# 200W_4FET_Load_v11.net
KiCad netlist of a schematic drawn in EAGLE
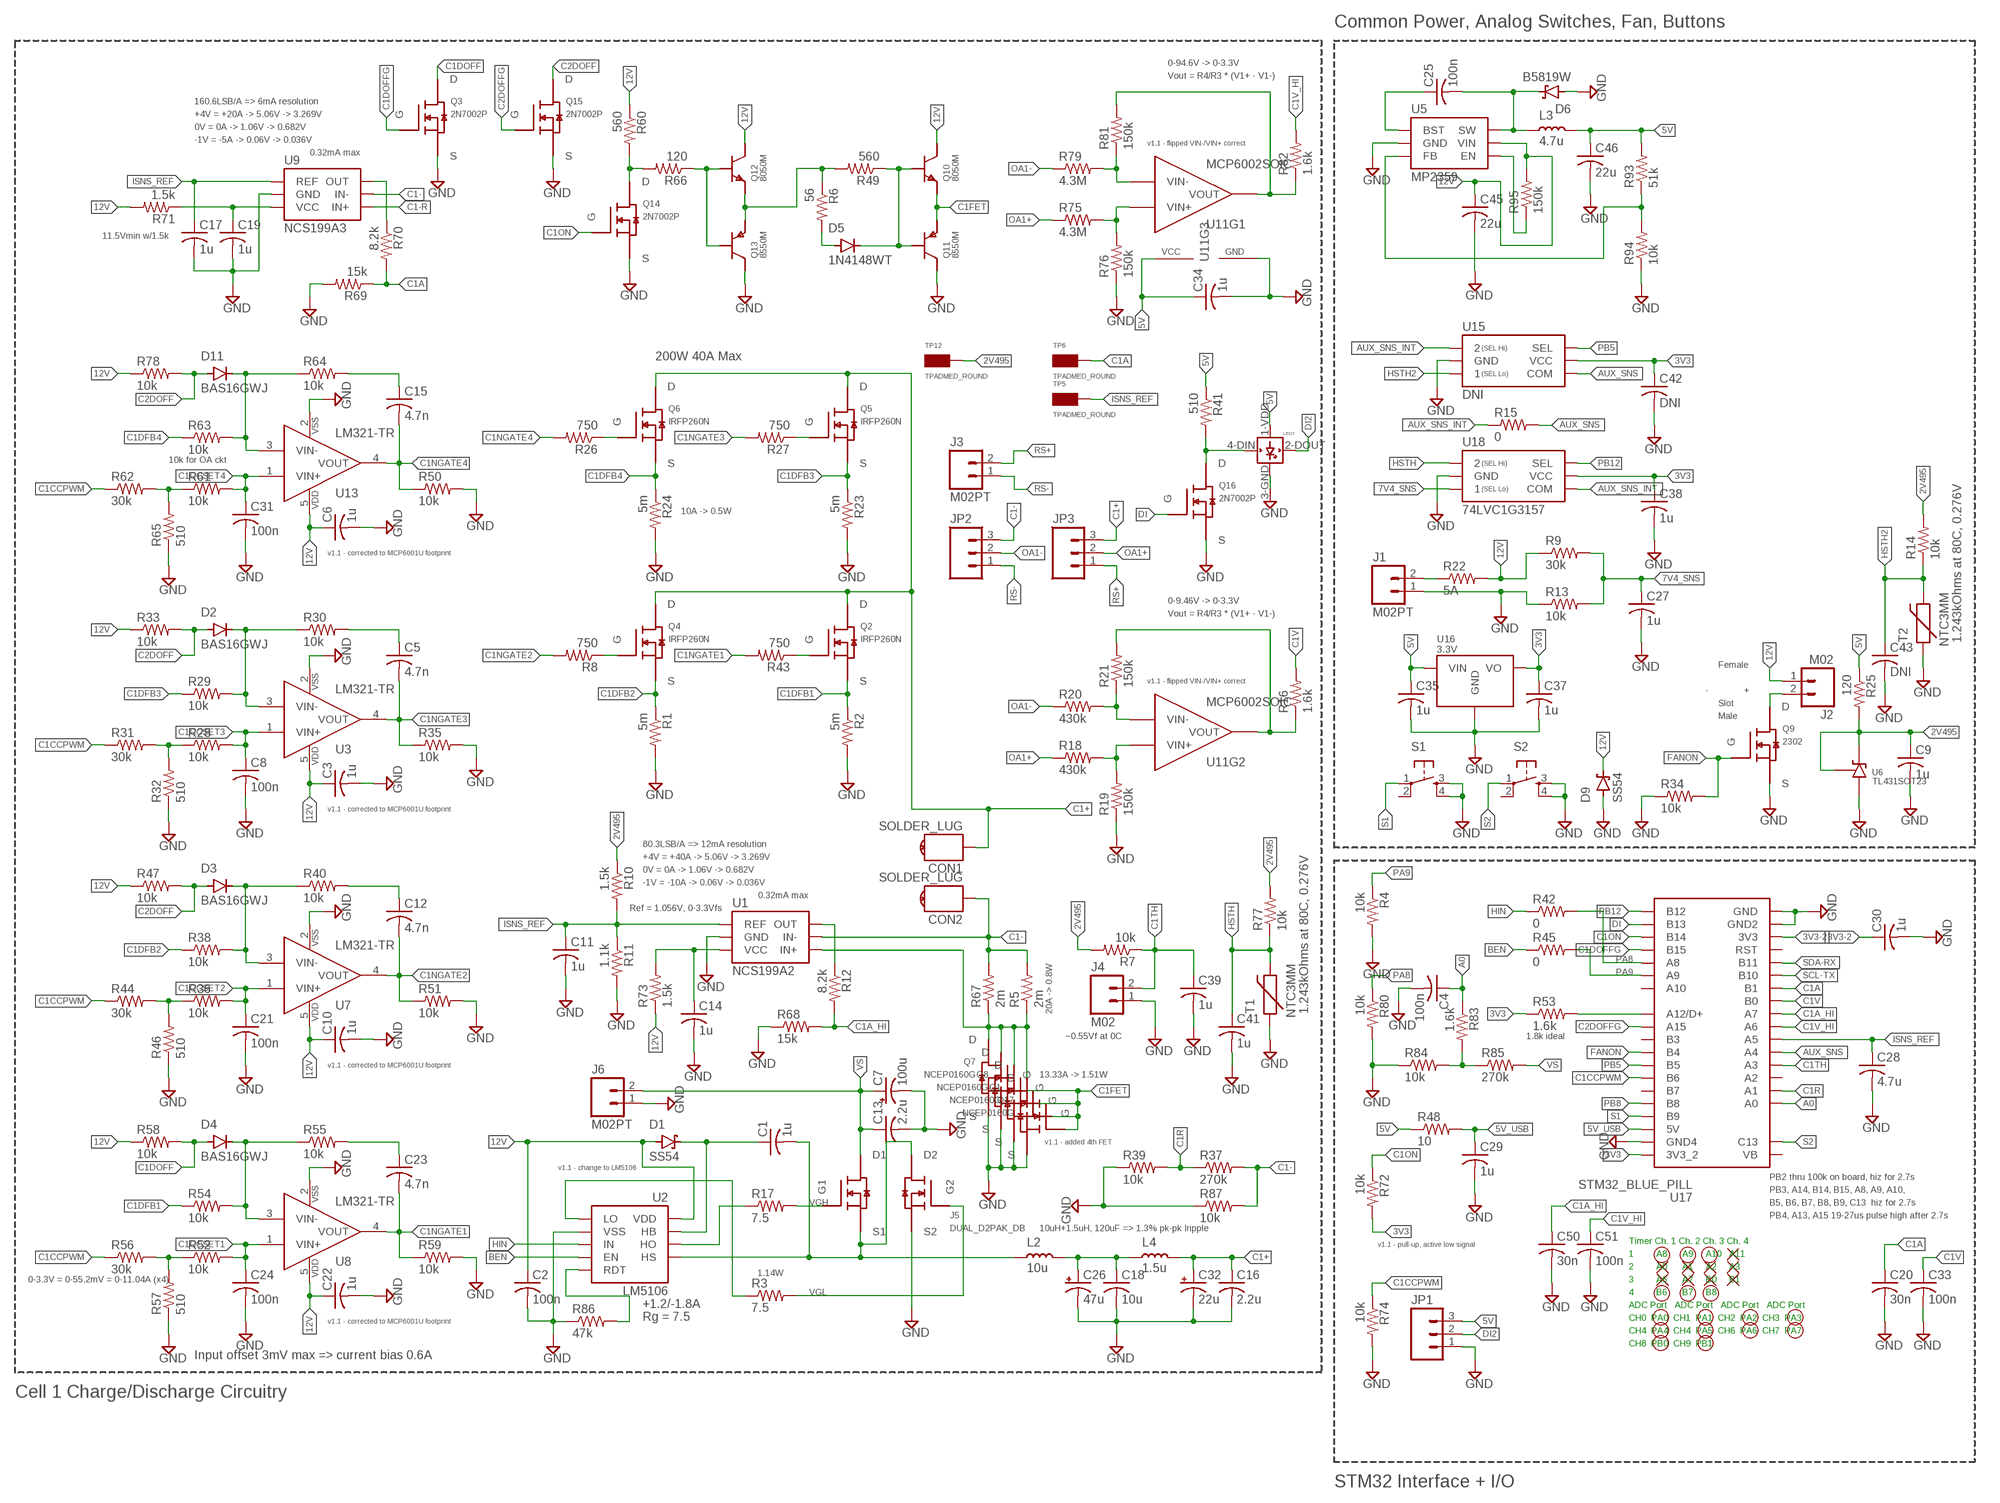
[diagram p0: schematic, sheet 1]

(export (version "E")
  (design (tool "Eeschema 10.0.6"))
  (components
    (comp (ref "C1")
      (value "1u")
      (footprint "eagle-import:C0603")
      (libsource (lib "eagle-import") (part "C-USC0603"))
    )
    (comp (ref "C2")
      (value "100n")
      (footprint "eagle-import:C0603")
      (libsource (lib "eagle-import") (part "C-USC0603"))
    )
    (comp (ref "C3")
      (value "1u")
      (footprint "eagle-import:C0402")
      (libsource (lib "eagle-import") (part "C-USC0402"))
    )
    (comp (ref "C4")
      (value "100n")
      (footprint "eagle-import:C0402")
      (libsource (lib "eagle-import") (part "C-USC0402"))
    )
    (comp (ref "C5")
      (value "4.7n")
      (footprint "eagle-import:C0402")
      (libsource (lib "eagle-import") (part "C-USC0402"))
    )
    (comp (ref "C6")
      (value "1u")
      (footprint "eagle-import:C0402")
      (libsource (lib "eagle-import") (part "C-USC0402"))
    )
    (comp (ref "C7")
      (value "100u")
      (footprint "eagle-import:E2,5-6E")
      (libsource (lib "eagle-import") (part "CPOL-USE2,5-6E"))
    )
    (comp (ref "C8")
      (value "100n")
      (footprint "eagle-import:C0402")
      (libsource (lib "eagle-import") (part "C-USC0402"))
    )
    (comp (ref "C9")
      (value "1u")
      (footprint "eagle-import:C0402")
      (libsource (lib "eagle-import") (part "C-USC0402"))
    )
    (comp (ref "C10")
      (value "1u")
      (footprint "eagle-import:C0402")
      (libsource (lib "eagle-import") (part "C-USC0402"))
    )
    (comp (ref "C11")
      (value "1u")
      (footprint "eagle-import:C0402")
      (libsource (lib "eagle-import") (part "C-USC0402"))
    )
    (comp (ref "C12")
      (value "4.7n")
      (footprint "eagle-import:C0402")
      (libsource (lib "eagle-import") (part "C-USC0402"))
    )
    (comp (ref "C13")
      (value "2.2u")
      (footprint "eagle-import:C1210")
      (libsource (lib "eagle-import") (part "C-USC1210"))
    )
    (comp (ref "C14")
      (value "1u")
      (footprint "eagle-import:C0402")
      (libsource (lib "eagle-import") (part "C-USC0402"))
    )
    (comp (ref "C15")
      (value "4.7n")
      (footprint "eagle-import:C0402")
      (libsource (lib "eagle-import") (part "C-USC0402"))
    )
    (comp (ref "C16")
      (value "2.2u")
      (footprint "eagle-import:C1210")
      (libsource (lib "eagle-import") (part "C-USC1210"))
    )
    (comp (ref "C17")
      (value "1u")
      (footprint "eagle-import:C0402")
      (libsource (lib "eagle-import") (part "C-USC0402"))
    )
    (comp (ref "C18")
      (value "10u")
      (footprint "eagle-import:C2220K")
      (libsource (lib "eagle-import") (part "C-USC2220K"))
    )
    (comp (ref "C19")
      (value "1u")
      (footprint "eagle-import:C0402")
      (libsource (lib "eagle-import") (part "C-USC0402"))
    )
    (comp (ref "C20")
      (value "30n")
      (footprint "eagle-import:C0402")
      (libsource (lib "eagle-import") (part "C-USC0402"))
    )
    (comp (ref "C21")
      (value "100n")
      (footprint "eagle-import:C0402")
      (libsource (lib "eagle-import") (part "C-USC0402"))
    )
    (comp (ref "C22")
      (value "1u")
      (footprint "eagle-import:C0402")
      (libsource (lib "eagle-import") (part "C-USC0402"))
    )
    (comp (ref "C23")
      (value "4.7n")
      (footprint "eagle-import:C0402")
      (libsource (lib "eagle-import") (part "C-USC0402"))
    )
    (comp (ref "C24")
      (value "100n")
      (footprint "eagle-import:C0402")
      (libsource (lib "eagle-import") (part "C-USC0402"))
    )
    (comp (ref "C25")
      (value "100n")
      (footprint "eagle-import:C0402")
      (libsource (lib "eagle-import") (part "C-USC0402"))
    )
    (comp (ref "C26")
      (value "47u")
      (footprint "eagle-import:E3,5-8")
      (libsource (lib "eagle-import") (part "CPOL-USE3.5-8"))
    )
    (comp (ref "C27")
      (value "1u")
      (footprint "eagle-import:C0402")
      (libsource (lib "eagle-import") (part "C-USC0402"))
    )
    (comp (ref "C28")
      (value "4.7u")
      (footprint "eagle-import:C0402")
      (libsource (lib "eagle-import") (part "C-USC0402"))
    )
    (comp (ref "C29")
      (value "1u")
      (footprint "eagle-import:C0402")
      (libsource (lib "eagle-import") (part "C-USC0402"))
    )
    (comp (ref "C30")
      (value "1u")
      (footprint "eagle-import:C0402")
      (libsource (lib "eagle-import") (part "C-USC0402"))
    )
    (comp (ref "C31")
      (value "100n")
      (footprint "eagle-import:C0402")
      (libsource (lib "eagle-import") (part "C-USC0402"))
    )
    (comp (ref "C32")
      (value "22u")
      (footprint "eagle-import:E2,5-6E")
      (libsource (lib "eagle-import") (part "CPOL-USE2,5-6E"))
    )
    (comp (ref "C33")
      (value "100n")
      (footprint "eagle-import:C0402")
      (libsource (lib "eagle-import") (part "C-USC0402"))
    )
    (comp (ref "C34")
      (value "1u")
      (footprint "eagle-import:C0402")
      (libsource (lib "eagle-import") (part "C-USC0402"))
    )
    (comp (ref "C35")
      (value "1u")
      (footprint "eagle-import:C0402")
      (libsource (lib "eagle-import") (part "C-USC0402"))
    )
    (comp (ref "C37")
      (value "1u")
      (footprint "eagle-import:C0402")
      (libsource (lib "eagle-import") (part "C-USC0402"))
    )
    (comp (ref "C38")
      (value "1u")
      (footprint "eagle-import:C0402")
      (libsource (lib "eagle-import") (part "C-USC0402"))
    )
    (comp (ref "C39")
      (value "1u")
      (footprint "eagle-import:C0402")
      (libsource (lib "eagle-import") (part "C-USC0402"))
    )
    (comp (ref "C41")
      (value "1u")
      (footprint "eagle-import:C0402")
      (libsource (lib "eagle-import") (part "C-USC0402"))
    )
    (comp (ref "C42")
      (value "DNI")
      (footprint "eagle-import:C0402")
      (libsource (lib "eagle-import") (part "C-USC0402"))
    )
    (comp (ref "C43")
      (value "DNI")
      (footprint "eagle-import:C0402")
      (libsource (lib "eagle-import") (part "C-USC0402"))
    )
    (comp (ref "C45")
      (value "22u")
      (footprint "eagle-import:C0805")
      (libsource (lib "eagle-import") (part "C-USC0805"))
    )
    (comp (ref "C46")
      (value "22u")
      (footprint "eagle-import:C0603")
      (libsource (lib "eagle-import") (part "C-USC0603"))
    )
    (comp (ref "C50")
      (value "30n")
      (footprint "eagle-import:C0402")
      (libsource (lib "eagle-import") (part "C-USC0402"))
    )
    (comp (ref "C51")
      (value "100n")
      (footprint "eagle-import:C0402")
      (libsource (lib "eagle-import") (part "C-USC0402"))
    )
    (comp (ref "CON1")
      (value "SOLDER_LUG")
      (footprint "eagle-import:M4_RA_SOLDTERM")
      (libsource (lib "eagle-import") (part "SOLDER_LUG"))
    )
    (comp (ref "CON2")
      (value "SOLDER_LUG")
      (footprint "eagle-import:M4_RA_SOLDTERM")
      (libsource (lib "eagle-import") (part "SOLDER_LUG"))
    )
    (comp (ref "D1")
      (value "SS54")
      (footprint "eagle-import:SMA")
      (libsource (lib "eagle-import") (part "SS54"))
    )
    (comp (ref "D2")
      (value "BAS16GWJ")
      (footprint "eagle-import:SOD323")
      (libsource (lib "eagle-import") (part "BAT60A"))
    )
    (comp (ref "D3")
      (value "BAS16GWJ")
      (footprint "eagle-import:SOD323")
      (libsource (lib "eagle-import") (part "BAT60A"))
    )
    (comp (ref "D4")
      (value "BAS16GWJ")
      (footprint "eagle-import:SOD323")
      (libsource (lib "eagle-import") (part "BAT60A"))
    )
    (comp (ref "D5")
      (value "1N4148WT")
      (footprint "eagle-import:SOD523")
      (libsource (lib "eagle-import") (part "1N4148WT"))
    )
    (comp (ref "D6")
      (value "B5819W")
      (footprint "eagle-import:SOD123W")
      (libsource (lib "eagle-import") (part "PMEG3020ER"))
    )
    (comp (ref "D9")
      (value "SS54")
      (footprint "eagle-import:SMA")
      (libsource (lib "eagle-import") (part "SS54"))
    )
    (comp (ref "D11")
      (value "BAS16GWJ")
      (footprint "eagle-import:SOD323")
      (libsource (lib "eagle-import") (part "BAT60A"))
    )
    (comp (ref "J1")
      (value "M02PT")
      (footprint "eagle-import:PHOENIXCONTACT1935161")
      (libsource (lib "eagle-import") (part "M02PT"))
    )
    (comp (ref "J2")
      (value "M02")
      (footprint "eagle-import:B2B-XH-A")
      (libsource (lib "eagle-import") (part "M02"))
    )
    (comp (ref "J3")
      (value "M02PT")
      (footprint "eagle-import:PHOENIXCONTACT1935161")
      (libsource (lib "eagle-import") (part "M02PT"))
    )
    (comp (ref "J4")
      (value "M02")
      (footprint "eagle-import:B2B-XH-A")
      (libsource (lib "eagle-import") (part "M02"))
    )
    (comp (ref "J5")
      (value "DUAL_D2PAK_DB")
      (footprint "eagle-import:DUAL_D2PAK_DB")
      (libsource (lib "eagle-import") (part "DUAL_D2PAK_DB"))
    )
    (comp (ref "J6")
      (value "M02PT")
      (footprint "eagle-import:PHOENIXCONTACT1935161")
      (libsource (lib "eagle-import") (part "M02PT"))
    )
    (comp (ref "JP1")
      (value "M03PTH")
      (footprint "eagle-import:1X03")
      (libsource (lib "eagle-import") (part "M03PTH"))
    )
    (comp (ref "JP2")
      (value "M03PTH")
      (footprint "eagle-import:1X03")
      (libsource (lib "eagle-import") (part "M03PTH"))
    )
    (comp (ref "JP3")
      (value "M03PTH")
      (footprint "eagle-import:1X03")
      (libsource (lib "eagle-import") (part "M03PTH"))
    )
    (comp (ref "L2")
      (value "10u")
      (footprint "eagle-import:INDUCTOR_13.8X12.7")
      (libsource (lib "eagle-import") (part "INDUCTOR13P8"))
    )
    (comp (ref "L3")
      (value "4.7u")
      (footprint "eagle-import:0805")
      (libsource (lib "eagle-import") (part "INDUCTOR0805"))
    )
    (comp (ref "L4")
      (value "1.5u")
      (footprint "eagle-import:INDUCTOR_7.4X6.6MM")
      (libsource (lib "eagle-import") (part "INDUCTOR"))
    )
    (comp (ref "LED7")
      (value "WS2812B")
      (footprint "eagle-import:WS2812B")
      (libsource (lib "eagle-import") (part "WS2812B"))
    )
    (comp (ref "Q1")
      (value "NCEP0160G")
      (footprint "eagle-import:DFN5X6-8L")
      (libsource (lib "eagle-import") (part "NCEP0160G"))
    )
    (comp (ref "Q2")
      (value "IRFP260N")
      (footprint "eagle-import:TO-247")
      (libsource (lib "eagle-import") (part "IRFP260N"))
    )
    (comp (ref "Q3")
      (value "2N7002P")
      (footprint "eagle-import:SOT23")
      (libsource (lib "eagle-import") (part "2N7002P"))
    )
    (comp (ref "Q4")
      (value "IRFP260N")
      (footprint "eagle-import:TO-247")
      (libsource (lib "eagle-import") (part "IRFP260N"))
    )
    (comp (ref "Q5")
      (value "IRFP260N")
      (footprint "eagle-import:TO-247")
      (libsource (lib "eagle-import") (part "IRFP260N"))
    )
    (comp (ref "Q6")
      (value "IRFP260N")
      (footprint "eagle-import:TO-247")
      (libsource (lib "eagle-import") (part "IRFP260N"))
    )
    (comp (ref "Q7")
      (value "NCEP0160G")
      (footprint "eagle-import:DFN5X6-8L")
      (libsource (lib "eagle-import") (part "NCEP0160G"))
    )
    (comp (ref "Q8")
      (value "NCEP0160G")
      (footprint "eagle-import:DFN5X6-8L")
      (libsource (lib "eagle-import") (part "NCEP0160G"))
    )
    (comp (ref "Q9")
      (value "2302")
      (footprint "eagle-import:SOT23")
      (libsource (lib "eagle-import") (part "2N7002P"))
    )
    (comp (ref "Q10")
      (value "8050M")
      (footprint "eagle-import:SOT23")
      (libsource (lib "eagle-import") (part "8050M"))
    )
    (comp (ref "Q11")
      (value "8550M")
      (footprint "eagle-import:SOT23")
      (libsource (lib "eagle-import") (part "8550M"))
    )
    (comp (ref "Q12")
      (value "8050M")
      (footprint "eagle-import:SOT23")
      (libsource (lib "eagle-import") (part "8050M"))
    )
    (comp (ref "Q13")
      (value "8550M")
      (footprint "eagle-import:SOT23")
      (libsource (lib "eagle-import") (part "8550M"))
    )
    (comp (ref "Q14")
      (value "2N7002P")
      (footprint "eagle-import:SOT23")
      (libsource (lib "eagle-import") (part "2N7002P"))
    )
    (comp (ref "Q15")
      (value "2N7002P")
      (footprint "eagle-import:SOT23")
      (libsource (lib "eagle-import") (part "2N7002P"))
    )
    (comp (ref "Q16")
      (value "2N7002P")
      (footprint "eagle-import:SOT23")
      (libsource (lib "eagle-import") (part "2N7002P"))
    )
    (comp (ref "Q17")
      (value "NCEP0160G")
      (footprint "eagle-import:DFN5X6-8L")
      (libsource (lib "eagle-import") (part "NCEP0160G"))
    )
    (comp (ref "R1")
      (value "5m")
      (footprint "eagle-import:R1206")
      (libsource (lib "eagle-import") (part "R-US_R1206"))
    )
    (comp (ref "R2")
      (value "5m")
      (footprint "eagle-import:R1206")
      (libsource (lib "eagle-import") (part "R-US_R1206"))
    )
    (comp (ref "R3")
      (value "7.5")
      (footprint "eagle-import:R2512")
      (libsource (lib "eagle-import") (part "R-US_R2512"))
    )
    (comp (ref "R4")
      (value "10k")
      (footprint "eagle-import:R0402")
      (libsource (lib "eagle-import") (part "R-US_R0402"))
    )
    (comp (ref "R5")
      (value "2m")
      (footprint "eagle-import:R2512")
      (libsource (lib "eagle-import") (part "R-US_R2512"))
    )
    (comp (ref "R6")
      (value "56")
      (footprint "eagle-import:R0402")
      (libsource (lib "eagle-import") (part "R-US_R0402"))
    )
    (comp (ref "R7")
      (value "10k")
      (footprint "eagle-import:R0402")
      (libsource (lib "eagle-import") (part "R-US_R0402"))
    )
    (comp (ref "R8")
      (value "750")
      (footprint "eagle-import:R0402")
      (libsource (lib "eagle-import") (part "R-US_R0402"))
    )
    (comp (ref "R9")
      (value "30k")
      (footprint "eagle-import:R0402")
      (libsource (lib "eagle-import") (part "R-US_R0402"))
    )
    (comp (ref "R10")
      (value "1.5k")
      (footprint "eagle-import:R0402")
      (libsource (lib "eagle-import") (part "R-US_R0402"))
    )
    (comp (ref "R11")
      (value "1.1k")
      (footprint "eagle-import:R0402")
      (libsource (lib "eagle-import") (part "R-US_R0402"))
    )
    (comp (ref "R12")
      (value "8.2k")
      (footprint "eagle-import:R0402")
      (libsource (lib "eagle-import") (part "R-US_R0402"))
    )
    (comp (ref "R13")
      (value "10k")
      (footprint "eagle-import:R0402")
      (libsource (lib "eagle-import") (part "R-US_R0402"))
    )
    (comp (ref "R14")
      (value "10k")
      (footprint "eagle-import:R0402")
      (libsource (lib "eagle-import") (part "R-US_R0402"))
    )
    (comp (ref "R15")
      (value "0")
      (footprint "eagle-import:R0402")
      (libsource (lib "eagle-import") (part "R-US_R0402"))
    )
    (comp (ref "R16")
      (value "1.6k")
      (footprint "eagle-import:R0402")
      (libsource (lib "eagle-import") (part "R-US_R0402"))
    )
    (comp (ref "R17")
      (value "7.5")
      (footprint "eagle-import:R2512")
      (libsource (lib "eagle-import") (part "R-US_R2512"))
    )
    (comp (ref "R18")
      (value "430k")
      (footprint "eagle-import:R0402")
      (libsource (lib "eagle-import") (part "R-US_R0402"))
    )
    (comp (ref "R19")
      (value "150k")
      (footprint "eagle-import:R0402")
      (libsource (lib "eagle-import") (part "R-US_R0402"))
    )
    (comp (ref "R20")
      (value "430k")
      (footprint "eagle-import:R0402")
      (libsource (lib "eagle-import") (part "R-US_R0402"))
    )
    (comp (ref "R21")
      (value "150k")
      (footprint "eagle-import:R0402")
      (libsource (lib "eagle-import") (part "R-US_R0402"))
    )
    (comp (ref "R22")
      (value "5A")
      (footprint "eagle-import:R1206")
      (libsource (lib "eagle-import") (part "R-US_R1206"))
    )
    (comp (ref "R23")
      (value "5m")
      (footprint "eagle-import:R1206")
      (libsource (lib "eagle-import") (part "R-US_R1206"))
    )
    (comp (ref "R24")
      (value "5m")
      (footprint "eagle-import:R1206")
      (libsource (lib "eagle-import") (part "R-US_R1206"))
    )
    (comp (ref "R25")
      (value "120")
      (footprint "eagle-import:R0402")
      (libsource (lib "eagle-import") (part "R-US_R0402"))
    )
    (comp (ref "R26")
      (value "750")
      (footprint "eagle-import:R0402")
      (libsource (lib "eagle-import") (part "R-US_R0402"))
    )
    (comp (ref "R27")
      (value "750")
      (footprint "eagle-import:R0402")
      (libsource (lib "eagle-import") (part "R-US_R0402"))
    )
    (comp (ref "R28")
      (value "10k")
      (footprint "eagle-import:R0402")
      (libsource (lib "eagle-import") (part "R-US_R0402"))
    )
    (comp (ref "R29")
      (value "10k")
      (footprint "eagle-import:R0402")
      (libsource (lib "eagle-import") (part "R-US_R0402"))
    )
    (comp (ref "R30")
      (value "10k")
      (footprint "eagle-import:R0402")
      (libsource (lib "eagle-import") (part "R-US_R0402"))
    )
    (comp (ref "R31")
      (value "30k")
      (footprint "eagle-import:R0402")
      (libsource (lib "eagle-import") (part "R-US_R0402"))
    )
    (comp (ref "R32")
      (value "510")
      (footprint "eagle-import:R0402")
      (libsource (lib "eagle-import") (part "R-US_R0402"))
    )
    (comp (ref "R33")
      (value "10k")
      (footprint "eagle-import:R0402")
      (libsource (lib "eagle-import") (part "R-US_R0402"))
    )
    (comp (ref "R34")
      (value "10k")
      (footprint "eagle-import:R0402")
      (libsource (lib "eagle-import") (part "R-US_R0402"))
    )
    (comp (ref "R35")
      (value "10k")
      (footprint "eagle-import:R0402")
      (libsource (lib "eagle-import") (part "R-US_R0402"))
    )
    (comp (ref "R36")
      (value "10k")
      (footprint "eagle-import:R0402")
      (libsource (lib "eagle-import") (part "R-US_R0402"))
    )
    (comp (ref "R37")
      (value "270k")
      (footprint "eagle-import:R0402")
      (libsource (lib "eagle-import") (part "R-US_R0402"))
    )
    (comp (ref "R38")
      (value "10k")
      (footprint "eagle-import:R0402")
      (libsource (lib "eagle-import") (part "R-US_R0402"))
    )
    (comp (ref "R39")
      (value "10k")
      (footprint "eagle-import:R0402")
      (libsource (lib "eagle-import") (part "R-US_R0402"))
    )
    (comp (ref "R40")
      (value "10k")
      (footprint "eagle-import:R0402")
      (libsource (lib "eagle-import") (part "R-US_R0402"))
    )
    (comp (ref "R41")
      (value "510")
      (footprint "eagle-import:R0402")
      (libsource (lib "eagle-import") (part "R-US_R0402"))
    )
    (comp (ref "R42")
      (value "0")
      (footprint "eagle-import:R0402")
      (libsource (lib "eagle-import") (part "R-US_R0402"))
    )
    (comp (ref "R43")
      (value "750")
      (footprint "eagle-import:R0402")
      (libsource (lib "eagle-import") (part "R-US_R0402"))
    )
    (comp (ref "R44")
      (value "30k")
      (footprint "eagle-import:R0402")
      (libsource (lib "eagle-import") (part "R-US_R0402"))
    )
    (comp (ref "R45")
      (value "0")
      (footprint "eagle-import:R0402")
      (libsource (lib "eagle-import") (part "R-US_R0402"))
    )
    (comp (ref "R46")
      (value "510")
      (footprint "eagle-import:R0402")
      (libsource (lib "eagle-import") (part "R-US_R0402"))
    )
    (comp (ref "R47")
      (value "10k")
      (footprint "eagle-import:R0402")
      (libsource (lib "eagle-import") (part "R-US_R0402"))
    )
    (comp (ref "R48")
      (value "10")
      (footprint "eagle-import:R0402")
      (libsource (lib "eagle-import") (part "R-US_R0402"))
    )
    (comp (ref "R49")
      (value "560")
      (footprint "eagle-import:R0402")
      (libsource (lib "eagle-import") (part "R-US_R0402"))
    )
    (comp (ref "R50")
      (value "10k")
      (footprint "eagle-import:R0402")
      (libsource (lib "eagle-import") (part "R-US_R0402"))
    )
    (comp (ref "R51")
      (value "10k")
      (footprint "eagle-import:R0402")
      (libsource (lib "eagle-import") (part "R-US_R0402"))
    )
    (comp (ref "R52")
      (value "10k")
      (footprint "eagle-import:R0402")
      (libsource (lib "eagle-import") (part "R-US_R0402"))
    )
    (comp (ref "R53")
      (value "1.6k")
      (footprint "eagle-import:R0402")
      (libsource (lib "eagle-import") (part "R-US_R0402"))
    )
    (comp (ref "R54")
      (value "10k")
      (footprint "eagle-import:R0402")
      (libsource (lib "eagle-import") (part "R-US_R0402"))
    )
    (comp (ref "R55")
      (value "10k")
      (footprint "eagle-import:R0402")
      (libsource (lib "eagle-import") (part "R-US_R0402"))
    )
    (comp (ref "R56")
      (value "30k")
      (footprint "eagle-import:R0402")
      (libsource (lib "eagle-import") (part "R-US_R0402"))
    )
    (comp (ref "R57")
      (value "510")
      (footprint "eagle-import:R0402")
      (libsource (lib "eagle-import") (part "R-US_R0402"))
    )
    (comp (ref "R58")
      (value "10k")
      (footprint "eagle-import:R0402")
      (libsource (lib "eagle-import") (part "R-US_R0402"))
    )
    (comp (ref "R59")
      (value "10k")
      (footprint "eagle-import:R0402")
      (libsource (lib "eagle-import") (part "R-US_R0402"))
    )
    (comp (ref "R60")
      (value "560")
      (footprint "eagle-import:R0402")
      (libsource (lib "eagle-import") (part "R-US_R0402"))
    )
    (comp (ref "R61")
      (value "10k")
      (footprint "eagle-import:R0402")
      (libsource (lib "eagle-import") (part "R-US_R0402"))
    )
    (comp (ref "R62")
      (value "30k")
      (footprint "eagle-import:R0402")
      (libsource (lib "eagle-import") (part "R-US_R0402"))
    )
    (comp (ref "R63")
      (value "10k")
      (footprint "eagle-import:R0402")
      (libsource (lib "eagle-import") (part "R-US_R0402"))
    )
    (comp (ref "R64")
      (value "10k")
      (footprint "eagle-import:R0402")
      (libsource (lib "eagle-import") (part "R-US_R0402"))
    )
    (comp (ref "R65")
      (value "510")
      (footprint "eagle-import:R0402")
      (libsource (lib "eagle-import") (part "R-US_R0402"))
    )
    (comp (ref "R66")
      (value "120")
      (footprint "eagle-import:R0402")
      (libsource (lib "eagle-import") (part "R-US_R0402"))
    )
    (comp (ref "R67")
      (value "2m")
      (footprint "eagle-import:R2512")
      (libsource (lib "eagle-import") (part "R-US_R2512"))
    )
    (comp (ref "R68")
      (value "15k")
      (footprint "eagle-import:R0402")
      (libsource (lib "eagle-import") (part "R-US_R0402"))
    )
    (comp (ref "R69")
      (value "15k")
      (footprint "eagle-import:R0402")
      (libsource (lib "eagle-import") (part "R-US_R0402"))
    )
    (comp (ref "R70")
      (value "8.2k")
      (footprint "eagle-import:R0402")
      (libsource (lib "eagle-import") (part "R-US_R0402"))
    )
    (comp (ref "R71")
      (value "1.5k")
      (footprint "eagle-import:R0402")
      (libsource (lib "eagle-import") (part "R-US_R0402"))
    )
    (comp (ref "R72")
      (value "10k")
      (footprint "eagle-import:R0402")
      (libsource (lib "eagle-import") (part "R-US_R0402"))
    )
    (comp (ref "R73")
      (value "1.5k")
      (footprint "eagle-import:R0402")
      (libsource (lib "eagle-import") (part "R-US_R0402"))
    )
    (comp (ref "R74")
      (value "10k")
      (footprint "eagle-import:R0402")
      (libsource (lib "eagle-import") (part "R-US_R0402"))
    )
    (comp (ref "R75")
      (value "4.3M")
      (footprint "eagle-import:R0402")
      (libsource (lib "eagle-import") (part "R-US_R0402"))
    )
    (comp (ref "R76")
      (value "150k")
      (footprint "eagle-import:R0402")
      (libsource (lib "eagle-import") (part "R-US_R0402"))
    )
    (comp (ref "R77")
      (value "10k")
      (footprint "eagle-import:R0402")
      (libsource (lib "eagle-import") (part "R-US_R0402"))
    )
    (comp (ref "R78")
      (value "10k")
      (footprint "eagle-import:R0402")
      (libsource (lib "eagle-import") (part "R-US_R0402"))
    )
    (comp (ref "R79")
      (value "4.3M")
      (footprint "eagle-import:R0402")
      (libsource (lib "eagle-import") (part "R-US_R0402"))
    )
    (comp (ref "R80")
      (value "10k")
      (footprint "eagle-import:R0402")
      (libsource (lib "eagle-import") (part "R-US_R0402"))
    )
    (comp (ref "R81")
      (value "150k")
      (footprint "eagle-import:R0402")
      (libsource (lib "eagle-import") (part "R-US_R0402"))
    )
    (comp (ref "R82")
      (value "1.6k")
      (footprint "eagle-import:R0402")
      (libsource (lib "eagle-import") (part "R-US_R0402"))
    )
    (comp (ref "R83")
      (value "1.6k")
      (footprint "eagle-import:R0402")
      (libsource (lib "eagle-import") (part "R-US_R0402"))
    )
    (comp (ref "R84")
      (value "10k")
      (footprint "eagle-import:R0402")
      (libsource (lib "eagle-import") (part "R-US_R0402"))
    )
    (comp (ref "R85")
      (value "270k")
      (footprint "eagle-import:R0402")
      (libsource (lib "eagle-import") (part "R-US_R0402"))
    )
    (comp (ref "R86")
      (value "47k")
      (footprint "eagle-import:R0402")
      (libsource (lib "eagle-import") (part "R-US_R0402"))
    )
    (comp (ref "R87")
      (value "10k")
      (footprint "eagle-import:R1206")
      (libsource (lib "eagle-import") (part "R-US_R1206"))
    )
    (comp (ref "R93")
      (value "51k")
      (footprint "eagle-import:R0402")
      (libsource (lib "eagle-import") (part "R-US_R0402"))
    )
    (comp (ref "R94")
      (value "10k")
      (footprint "eagle-import:R0402")
      (libsource (lib "eagle-import") (part "R-US_R0402"))
    )
    (comp (ref "R95")
      (value "150k")
      (footprint "eagle-import:R0402")
      (libsource (lib "eagle-import") (part "R-US_R0402"))
    )
    (comp (ref "S1")
      (value "TAC_SWITCHSMD")
      (footprint "eagle-import:TACTILE_SWITCH_SMD")
      (libsource (lib "eagle-import") (part "TAC_SWITCHSMD"))
    )
    (comp (ref "S2")
      (value "TAC_SWITCHSMD")
      (footprint "eagle-import:TACTILE_SWITCH_SMD")
      (libsource (lib "eagle-import") (part "TAC_SWITCHSMD"))
    )
    (comp (ref "T1")
      (value "NTC3MM")
      (footprint "eagle-import:THERMISTOR_3MMX3MM")
      (libsource (lib "eagle-import") (part "PTCNTC3MM"))
    )
    (comp (ref "T2")
      (value "NTC3MM")
      (footprint "eagle-import:THERMISTOR_3MMX3MM")
      (libsource (lib "eagle-import") (part "PTCNTC3MM"))
    )
    (comp (ref "TP5")
      (value "TPADMED_ROUND")
      (footprint "eagle-import:TPAD_MED_ROUND")
      (libsource (lib "eagle-import") (part "TPADMED_ROUND"))
    )
    (comp (ref "TP6")
      (value "TPADMED_ROUND")
      (footprint "eagle-import:TPAD_MED_ROUND")
      (libsource (lib "eagle-import") (part "TPADMED_ROUND"))
    )
    (comp (ref "TP12")
      (value "TPADMED_ROUND")
      (footprint "eagle-import:TPAD_MED_ROUND")
      (libsource (lib "eagle-import") (part "TPADMED_ROUND"))
    )
    (comp (ref "U1")
      (value "NCS199A2")
      (footprint "eagle-import:SOT-363")
      (libsource (lib "eagle-import") (part "INA214"))
    )
    (comp (ref "U2")
      (value "LM5106")
      (footprint "eagle-import:10-TSSOP")
      (libsource (lib "eagle-import") (part "LM5106"))
    )
    (comp (ref "U3")
      (value "LM321-TR")
      (footprint "eagle-import:SOT23-5")
      (libsource (lib "eagle-import") (part "MCP6001U"))
    )
    (comp (ref "U5")
      (value "MP2359")
      (footprint "eagle-import:SOT23-6")
      (libsource (lib "eagle-import") (part "JW5052C"))
    )
    (comp (ref "U6")
      (value "TL431SOT23")
      (footprint "eagle-import:SOT23")
      (libsource (lib "eagle-import") (part "TL431SOT23"))
    )
    (comp (ref "U7")
      (value "LM321-TR")
      (footprint "eagle-import:SOT23-5")
      (libsource (lib "eagle-import") (part "MCP6001U"))
    )
    (comp (ref "U8")
      (value "LM321-TR")
      (footprint "eagle-import:SOT23-5")
      (libsource (lib "eagle-import") (part "MCP6001U"))
    )
    (comp (ref "U9")
      (value "NCS199A3")
      (footprint "eagle-import:SOT-363")
      (libsource (lib "eagle-import") (part "INA214"))
    )
    (comp (ref "U11")
      (value "MCP6002SOIC")
      (footprint "eagle-import:8-SOIC")
      (libsource (lib "eagle-import") (part "MCP6002SOIC"))
    )
    (comp (ref "U13")
      (value "LM321-TR")
      (footprint "eagle-import:SOT23-5")
      (libsource (lib "eagle-import") (part "MCP6001U"))
    )
    (comp (ref "U15")
      (value "DNI")
      (footprint "eagle-import:SC70-6")
      (libsource (lib "eagle-import") (part "SN74LVC1G3157SC70-6"))
    )
    (comp (ref "U16")
      (value "3.3V")
      (footprint "eagle-import:SOT-89")
      (libsource (lib "eagle-import") (part "AP1117UR133-B"))
    )
    (comp (ref "U17")
      (value "STM32_BLUE_PILL")
      (footprint "eagle-import:STM32_BLUE_PILL_USABLE")
      (libsource (lib "eagle-import") (part "STM32_BLUE_PILL"))
    )
    (comp (ref "U18")
      (value "74LVC1G3157")
      (footprint "eagle-import:SC70-6")
      (libsource (lib "eagle-import") (part "SN74LVC1G3157SC70-6"))
    )
  )
  (nets
    (net (code "1") (name "/VGH") (class "Default")
      (node (ref "J5") (pin "G1") (pinfunction "G1_G1") (pintype "bidirectional"))
      (node (ref "R17") (pin "2") (pinfunction "2_2") (pintype "passive"))
    )
    (net (code "2") (name "/VGL") (class "Default")
      (node (ref "J5") (pin "G2") (pinfunction "G2_G2") (pintype "bidirectional"))
      (node (ref "R3") (pin "2") (pinfunction "2_2") (pintype "passive"))
    )
    (net (code "3") (name "2V495") (class "Default")
      (node (ref "C9") (pin "1") (pinfunction "1_1") (pintype "passive"))
      (node (ref "R10") (pin "1") (pinfunction "1_1") (pintype "passive"))
      (node (ref "R14") (pin "2") (pinfunction "2_2") (pintype "passive"))
      (node (ref "R25") (pin "2") (pinfunction "2_2") (pintype "passive"))
      (node (ref "R7") (pin "2") (pinfunction "2_2") (pintype "passive"))
      (node (ref "R77") (pin "2") (pinfunction "2_2") (pintype "passive"))
      (node (ref "TP12") (pin "1") (pinfunction "1_1") (pintype "bidirectional"))
      (node (ref "U6") (pin "1") (pinfunction "K_1") (pintype "passive"))
      (node (ref "U6") (pin "2") (pinfunction "REF_2") (pintype "passive"))
    )
    (net (code "4") (name "3V3") (class "Default")
      (node (ref "C37") (pin "1") (pinfunction "1_1") (pintype "passive"))
      (node (ref "C38") (pin "1") (pinfunction "1_1") (pintype "passive"))
      (node (ref "C42") (pin "1") (pinfunction "1_1") (pintype "passive"))
      (node (ref "R53") (pin "1") (pinfunction "1_1") (pintype "passive"))
      (node (ref "R72") (pin "2") (pinfunction "2_2") (pintype "passive"))
      (node (ref "U15") (pin "5") (pinfunction "VCC_5") (pintype "bidirectional"))
      (node (ref "U16") (pin "1") (pinfunction "VO_1") (pintype "bidirectional"))
      (node (ref "U17") (pin "3V3_2") (pinfunction "3V3_2_3V3_2") (pintype "bidirectional"))
      (node (ref "U18") (pin "5") (pinfunction "VCC_5") (pintype "bidirectional"))
    )
    (net (code "5") (name "3V3-2") (class "Default")
      (node (ref "C30") (pin "1") (pinfunction "1_1") (pintype "passive"))
      (node (ref "U17") (pin "3V3") (pinfunction "3V3_3V3") (pintype "bidirectional"))
    )
    (net (code "6") (name "5V") (class "Default")
      (node (ref "C34") (pin "1") (pinfunction "1_1") (pintype "passive"))
      (node (ref "C35") (pin "1") (pinfunction "1_1") (pintype "passive"))
      (node (ref "C46") (pin "1") (pinfunction "1_1") (pintype "passive"))
      (node (ref "JP1") (pin "3") (pinfunction "3_3") (pintype "passive"))
      (node (ref "L3") (pin "2") (pinfunction "P$2_2") (pintype "passive"))
      (node (ref "LED7") (pin "1-VDD") (pinfunction "VDD_1-VDD") (pintype "bidirectional"))
      (node (ref "R25") (pin "1") (pinfunction "1_1") (pintype "passive"))
      (node (ref "R41") (pin "1") (pinfunction "1_1") (pintype "passive"))
      (node (ref "R48") (pin "1") (pinfunction "1_1") (pintype "passive"))
      (node (ref "R93") (pin "2") (pinfunction "2_2") (pintype "passive"))
      (node (ref "U11") (pin "8") (pinfunction "VCC_8") (pintype "power_in"))
      (node (ref "U16") (pin "3") (pinfunction "VIN_3") (pintype "bidirectional"))
    )
    (net (code "7") (name "5V_USB") (class "Default")
      (node (ref "C29") (pin "1") (pinfunction "1_1") (pintype "passive"))
      (node (ref "R48") (pin "2") (pinfunction "2_2") (pintype "passive"))
      (node (ref "U17") (pin "5V") (pinfunction "5V_5V") (pintype "bidirectional"))
    )
    (net (code "8") (name "7V4_SNS") (class "Default")
      (node (ref "C27") (pin "1") (pinfunction "1_1") (pintype "passive"))
      (node (ref "R13") (pin "2") (pinfunction "2_2") (pintype "passive"))
      (node (ref "R9") (pin "2") (pinfunction "2_2") (pintype "passive"))
      (node (ref "U18") (pin "3") (pinfunction "1_3") (pintype "bidirectional"))
    )
    (net (code "9") (name "12V") (class "Default")
      (node (ref "C10") (pin "1") (pinfunction "1_1") (pintype "passive"))
      (node (ref "C2") (pin "1") (pinfunction "1_1") (pintype "passive"))
      (node (ref "C22") (pin "1") (pinfunction "1_1") (pintype "passive"))
      (node (ref "C3") (pin "1") (pinfunction "1_1") (pintype "passive"))
      (node (ref "C45") (pin "1") (pinfunction "1_1") (pintype "passive"))
      (node (ref "C6") (pin "1") (pinfunction "1_1") (pintype "passive"))
      (node (ref "D1") (pin "A") (pinfunction "ANODE_A") (pintype "passive"))
      (node (ref "D9") (pin "K") (pinfunction "CATHODE_K") (pintype "passive"))
      (node (ref "J2") (pin "1") (pinfunction "1_1") (pintype "passive"))
      (node (ref "Q10") (pin "3") (pinfunction "C_3") (pintype "bidirectional"))
      (node (ref "Q12") (pin "3") (pinfunction "C_3") (pintype "bidirectional"))
      (node (ref "R22") (pin "2") (pinfunction "2_2") (pintype "passive"))
      (node (ref "R33") (pin "1") (pinfunction "1_1") (pintype "passive"))
      (node (ref "R47") (pin "1") (pinfunction "1_1") (pintype "passive"))
      (node (ref "R58") (pin "1") (pinfunction "1_1") (pintype "passive"))
      (node (ref "R60") (pin "1") (pinfunction "1_1") (pintype "passive"))
      (node (ref "R71") (pin "2") (pinfunction "2_2") (pintype "passive"))
      (node (ref "R73") (pin "1") (pinfunction "1_1") (pintype "passive"))
      (node (ref "R78") (pin "1") (pinfunction "1_1") (pintype "passive"))
      (node (ref "R9") (pin "1") (pinfunction "1_1") (pintype "passive"))
      (node (ref "R95") (pin "2") (pinfunction "2_2") (pintype "passive"))
      (node (ref "U13") (pin "5") (pinfunction "VDD_5") (pintype "bidirectional"))
      (node (ref "U2") (pin "1") (pinfunction "VDD_1") (pintype "bidirectional"))
      (node (ref "U3") (pin "5") (pinfunction "VDD_5") (pintype "bidirectional"))
      (node (ref "U5") (pin "5") (pinfunction "VIN_5") (pintype "bidirectional"))
      (node (ref "U7") (pin "5") (pinfunction "VDD_5") (pintype "bidirectional"))
      (node (ref "U8") (pin "5") (pinfunction "VDD_5") (pintype "bidirectional"))
    )
    (net (code "10") (name "A0") (class "Default")
      (node (ref "C4") (pin "1") (pinfunction "1_1") (pintype "passive"))
      (node (ref "R83") (pin "1") (pinfunction "1_1") (pintype "passive"))
      (node (ref "U17") (pin "A0") (pinfunction "A0_A0") (pintype "bidirectional"))
    )
    (net (code "11") (name "AUX_SNS") (class "Default")
      (node (ref "R15") (pin "2") (pinfunction "2_2") (pintype "passive"))
      (node (ref "U15") (pin "4") (pinfunction "COM_4") (pintype "bidirectional"))
      (node (ref "U17") (pin "A4") (pinfunction "A4_A4") (pintype "bidirectional"))
    )
    (net (code "12") (name "AUX_SNS_INT") (class "Default")
      (node (ref "R15") (pin "1") (pinfunction "1_1") (pintype "passive"))
      (node (ref "U15") (pin "1") (pinfunction "2_1") (pintype "bidirectional"))
      (node (ref "U18") (pin "4") (pinfunction "COM_4") (pintype "bidirectional"))
    )
    (net (code "13") (name "BEN") (class "Default")
      (node (ref "R45") (pin "1") (pinfunction "1_1") (pintype "passive"))
      (node (ref "U2") (pin "7") (pinfunction "EN_7") (pintype "bidirectional"))
    )
    (net (code "14") (name "C1+") (class "Default")
      (node (ref "C16") (pin "1") (pinfunction "1_1") (pintype "passive"))
      (node (ref "C32") (pin "+") (pinfunction "+_+") (pintype "passive"))
      (node (ref "CON1") (pin "P$1") (pinfunction "P$1_P$1") (pintype "bidirectional"))
      (node (ref "CON1") (pin "P$2") (pinfunction "P$1_P$2") (pintype "bidirectional"))
      (node (ref "CON1") (pin "P$3") (pinfunction "P$1_P$3") (pintype "bidirectional"))
      (node (ref "CON1") (pin "P$4") (pinfunction "P$1_P$4") (pintype "bidirectional"))
      (node (ref "JP3") (pin "3") (pinfunction "3_3") (pintype "passive"))
      (node (ref "L4") (pin "2") (pinfunction "P$2_2") (pintype "passive"))
      (node (ref "Q2") (pin "2") (pinfunction "D_2") (pintype "bidirectional"))
      (node (ref "Q4") (pin "2") (pinfunction "D_2") (pintype "bidirectional"))
      (node (ref "Q5") (pin "2") (pinfunction "D_2") (pintype "bidirectional"))
      (node (ref "Q6") (pin "2") (pinfunction "D_2") (pintype "bidirectional"))
    )
    (net (code "15") (name "C1-") (class "Default")
      (node (ref "CON2") (pin "P$1") (pinfunction "P$1_P$1") (pintype "bidirectional"))
      (node (ref "CON2") (pin "P$2") (pinfunction "P$1_P$2") (pintype "bidirectional"))
      (node (ref "CON2") (pin "P$3") (pinfunction "P$1_P$3") (pintype "bidirectional"))
      (node (ref "CON2") (pin "P$4") (pinfunction "P$1_P$4") (pintype "bidirectional"))
      (node (ref "JP2") (pin "3") (pinfunction "3_3") (pintype "passive"))
      (node (ref "R37") (pin "2") (pinfunction "2_2") (pintype "passive"))
      (node (ref "R5") (pin "2") (pinfunction "2_2") (pintype "passive"))
      (node (ref "R67") (pin "2") (pinfunction "2_2") (pintype "passive"))
      (node (ref "R87") (pin "2") (pinfunction "2_2") (pintype "passive"))
      (node (ref "U1") (pin "5") (pinfunction "IN-_5") (pintype "bidirectional"))
      (node (ref "U9") (pin "5") (pinfunction "IN-_5") (pintype "bidirectional"))
    )
    (net (code "16") (name "C1-R") (class "Default")
      (node (ref "Q1") (pin "EP") (pinfunction "D_EP") (pintype "bidirectional"))
      (node (ref "Q1") (pin "EP-TL") (pinfunction "D_EP-TL") (pintype "bidirectional"))
      (node (ref "Q1") (pin "EP-TLL") (pinfunction "D_EP-TLL") (pintype "bidirectional"))
      (node (ref "Q1") (pin "EP-TR") (pinfunction "D_EP-TR") (pintype "bidirectional"))
      (node (ref "Q1") (pin "EP-TRR") (pinfunction "D_EP-TRR") (pintype "bidirectional"))
      (node (ref "Q17") (pin "EP") (pinfunction "D_EP") (pintype "bidirectional"))
      (node (ref "Q17") (pin "EP-TL") (pinfunction "D_EP-TL") (pintype "bidirectional"))
      (node (ref "Q17") (pin "EP-TLL") (pinfunction "D_EP-TLL") (pintype "bidirectional"))
      (node (ref "Q17") (pin "EP-TR") (pinfunction "D_EP-TR") (pintype "bidirectional"))
      (node (ref "Q17") (pin "EP-TRR") (pinfunction "D_EP-TRR") (pintype "bidirectional"))
      (node (ref "Q7") (pin "EP") (pinfunction "D_EP") (pintype "bidirectional"))
      (node (ref "Q7") (pin "EP-TL") (pinfunction "D_EP-TL") (pintype "bidirectional"))
      (node (ref "Q7") (pin "EP-TLL") (pinfunction "D_EP-TLL") (pintype "bidirectional"))
      (node (ref "Q7") (pin "EP-TR") (pinfunction "D_EP-TR") (pintype "bidirectional"))
      (node (ref "Q7") (pin "EP-TRR") (pinfunction "D_EP-TRR") (pintype "bidirectional"))
      (node (ref "Q8") (pin "EP") (pinfunction "D_EP") (pintype "bidirectional"))
      (node (ref "Q8") (pin "EP-TL") (pinfunction "D_EP-TL") (pintype "bidirectional"))
      (node (ref "Q8") (pin "EP-TLL") (pinfunction "D_EP-TLL") (pintype "bidirectional"))
      (node (ref "Q8") (pin "EP-TR") (pinfunction "D_EP-TR") (pintype "bidirectional"))
      (node (ref "Q8") (pin "EP-TRR") (pinfunction "D_EP-TRR") (pintype "bidirectional"))
      (node (ref "R5") (pin "1") (pinfunction "1_1") (pintype "passive"))
      (node (ref "R67") (pin "1") (pinfunction "1_1") (pintype "passive"))
      (node (ref "U1") (pin "4") (pinfunction "IN+_4") (pintype "bidirectional"))
      (node (ref "U9") (pin "4") (pinfunction "IN+_4") (pintype "bidirectional"))
    )
    (net (code "17") (name "C1A") (class "Default")
      (node (ref "C20") (pin "1") (pinfunction "1_1") (pintype "passive"))
      (node (ref "R69") (pin "1") (pinfunction "1_1") (pintype "passive"))
      (node (ref "R70") (pin "2") (pinfunction "2_2") (pintype "passive"))
      (node (ref "TP6") (pin "1") (pinfunction "1_1") (pintype "bidirectional"))
      (node (ref "U17") (pin "B1") (pinfunction "B1_B1") (pintype "bidirectional"))
    )
    (net (code "18") (name "C1A_HI") (class "Default")
      (node (ref "C50") (pin "1") (pinfunction "1_1") (pintype "passive"))
      (node (ref "R12") (pin "2") (pinfunction "2_2") (pintype "passive"))
      (node (ref "R68") (pin "2") (pinfunction "2_2") (pintype "passive"))
      (node (ref "U17") (pin "A7") (pinfunction "A7_A7") (pintype "bidirectional"))
    )
    (net (code "19") (name "C1CCPWM") (class "Default")
      (node (ref "R31") (pin "1") (pinfunction "1_1") (pintype "passive"))
      (node (ref "R44") (pin "1") (pinfunction "1_1") (pintype "passive"))
      (node (ref "R56") (pin "1") (pinfunction "1_1") (pintype "passive"))
      (node (ref "R62") (pin "1") (pinfunction "1_1") (pintype "passive"))
      (node (ref "R74") (pin "1") (pinfunction "1_1") (pintype "passive"))
      (node (ref "U17") (pin "B6") (pinfunction "B6_B6") (pintype "bidirectional"))
    )
    (net (code "20") (name "C1CCSET1") (class "Default")
      (node (ref "C24") (pin "1") (pinfunction "1_1") (pintype "passive"))
      (node (ref "R52") (pin "2") (pinfunction "2_2") (pintype "passive"))
      (node (ref "U8") (pin "1") (pinfunction "VIN+_1") (pintype "bidirectional"))
    )
    (net (code "21") (name "C1CCSET2") (class "Default")
      (node (ref "C21") (pin "1") (pinfunction "1_1") (pintype "passive"))
      (node (ref "R36") (pin "2") (pinfunction "2_2") (pintype "passive"))
      (node (ref "U7") (pin "1") (pinfunction "VIN+_1") (pintype "bidirectional"))
    )
    (net (code "22") (name "C1CCSET3") (class "Default")
      (node (ref "C8") (pin "1") (pinfunction "1_1") (pintype "passive"))
      (node (ref "R28") (pin "2") (pinfunction "2_2") (pintype "passive"))
      (node (ref "U3") (pin "1") (pinfunction "VIN+_1") (pintype "bidirectional"))
    )
    (net (code "23") (name "C1CCSET4") (class "Default")
      (node (ref "C31") (pin "1") (pinfunction "1_1") (pintype "passive"))
      (node (ref "R61") (pin "2") (pinfunction "2_2") (pintype "passive"))
      (node (ref "U13") (pin "1") (pinfunction "VIN+_1") (pintype "bidirectional"))
    )
    (net (code "24") (name "C1DFB1") (class "Default")
      (node (ref "Q2") (pin "3") (pinfunction "S_3") (pintype "bidirectional"))
      (node (ref "R2") (pin "1") (pinfunction "1_1") (pintype "passive"))
      (node (ref "R54") (pin "1") (pinfunction "1_1") (pintype "passive"))
    )
    (net (code "25") (name "C1DFB2") (class "Default")
      (node (ref "Q4") (pin "3") (pinfunction "S_3") (pintype "bidirectional"))
      (node (ref "R1") (pin "1") (pinfunction "1_1") (pintype "passive"))
      (node (ref "R38") (pin "1") (pinfunction "1_1") (pintype "passive"))
    )
    (net (code "26") (name "C1DFB3") (class "Default")
      (node (ref "Q5") (pin "3") (pinfunction "S_3") (pintype "bidirectional"))
      (node (ref "R23") (pin "1") (pinfunction "1_1") (pintype "passive"))
      (node (ref "R29") (pin "1") (pinfunction "1_1") (pintype "passive"))
    )
    (net (code "27") (name "C1DFB4") (class "Default")
      (node (ref "Q6") (pin "3") (pinfunction "S_3") (pintype "bidirectional"))
      (node (ref "R24") (pin "1") (pinfunction "1_1") (pintype "passive"))
      (node (ref "R63") (pin "1") (pinfunction "1_1") (pintype "passive"))
    )
    (net (code "28") (name "C1DOFF") (class "Default")
      (node (ref "D4") (pin "A") (pinfunction "ANODE_A") (pintype "passive"))
      (node (ref "Q3") (pin "3") (pinfunction "D_3") (pintype "bidirectional"))
      (node (ref "R58") (pin "2") (pinfunction "2_2") (pintype "passive"))
    )
    (net (code "29") (name "C1DOFFG") (class "Default")
      (node (ref "Q3") (pin "1") (pinfunction "G_1") (pintype "bidirectional"))
      (node (ref "U17") (pin "B15") (pinfunction "B15_B15") (pintype "bidirectional"))
    )
    (net (code "30") (name "C1FET") (class "Default")
      (node (ref "Q1") (pin "4") (pinfunction "G_4") (pintype "bidirectional"))
      (node (ref "Q10") (pin "2") (pinfunction "E_2") (pintype "bidirectional"))
      (node (ref "Q11") (pin "2") (pinfunction "E_2") (pintype "bidirectional"))
      (node (ref "Q17") (pin "4") (pinfunction "G_4") (pintype "bidirectional"))
      (node (ref "Q7") (pin "4") (pinfunction "G_4") (pintype "bidirectional"))
      (node (ref "Q8") (pin "4") (pinfunction "G_4") (pintype "bidirectional"))
    )
    (net (code "31") (name "C1NGATE1") (class "Default")
      (node (ref "C23") (pin "2") (pinfunction "2_2") (pintype "passive"))
      (node (ref "R43") (pin "2") (pinfunction "2_2") (pintype "passive"))
      (node (ref "R59") (pin "1") (pinfunction "1_1") (pintype "passive"))
      (node (ref "U8") (pin "4") (pinfunction "VOUT_4") (pintype "bidirectional"))
    )
    (net (code "32") (name "C1NGATE2") (class "Default")
      (node (ref "C12") (pin "2") (pinfunction "2_2") (pintype "passive"))
      (node (ref "R51") (pin "1") (pinfunction "1_1") (pintype "passive"))
      (node (ref "R8") (pin "2") (pinfunction "2_2") (pintype "passive"))
      (node (ref "U7") (pin "4") (pinfunction "VOUT_4") (pintype "bidirectional"))
    )
    (net (code "33") (name "C1NGATE3") (class "Default")
      (node (ref "C5") (pin "2") (pinfunction "2_2") (pintype "passive"))
      (node (ref "R27") (pin "2") (pinfunction "2_2") (pintype "passive"))
      (node (ref "R35") (pin "1") (pinfunction "1_1") (pintype "passive"))
      (node (ref "U3") (pin "4") (pinfunction "VOUT_4") (pintype "bidirectional"))
    )
    (net (code "34") (name "C1NGATE4") (class "Default")
      (node (ref "C15") (pin "2") (pinfunction "2_2") (pintype "passive"))
      (node (ref "R26") (pin "2") (pinfunction "2_2") (pintype "passive"))
      (node (ref "R50") (pin "1") (pinfunction "1_1") (pintype "passive"))
      (node (ref "U13") (pin "4") (pinfunction "VOUT_4") (pintype "bidirectional"))
    )
    (net (code "35") (name "C1ON") (class "Default")
      (node (ref "Q14") (pin "1") (pinfunction "G_1") (pintype "bidirectional"))
      (node (ref "R72") (pin "1") (pinfunction "1_1") (pintype "passive"))
      (node (ref "U17") (pin "B14") (pinfunction "B14_B14") (pintype "bidirectional"))
    )
    (net (code "36") (name "C1R") (class "Default")
      (node (ref "R37") (pin "1") (pinfunction "1_1") (pintype "passive"))
      (node (ref "R39") (pin "2") (pinfunction "2_2") (pintype "passive"))
      (node (ref "U17") (pin "A1") (pinfunction "A1_A1") (pintype "bidirectional"))
    )
    (net (code "37") (name "C1TH") (class "Default")
      (node (ref "C39") (pin "1") (pinfunction "1_1") (pintype "passive"))
      (node (ref "J4") (pin "2") (pinfunction "2_2") (pintype "passive"))
      (node (ref "R7") (pin "1") (pinfunction "1_1") (pintype "passive"))
      (node (ref "U17") (pin "A3") (pinfunction "A3_A3") (pintype "bidirectional"))
    )
    (net (code "38") (name "C1V") (class "Default")
      (node (ref "C33") (pin "1") (pinfunction "1_1") (pintype "passive"))
      (node (ref "R16") (pin "2") (pinfunction "2_2") (pintype "passive"))
      (node (ref "U17") (pin "B0") (pinfunction "B0_B0") (pintype "bidirectional"))
    )
    (net (code "39") (name "C1V_HI") (class "Default")
      (node (ref "C51") (pin "1") (pinfunction "1_1") (pintype "passive"))
      (node (ref "R82") (pin "2") (pinfunction "2_2") (pintype "passive"))
      (node (ref "U17") (pin "A6") (pinfunction "A6_A6") (pintype "bidirectional"))
    )
    (net (code "40") (name "C2DOFF") (class "Default")
      (node (ref "D11") (pin "A") (pinfunction "ANODE_A") (pintype "passive"))
      (node (ref "D2") (pin "A") (pinfunction "ANODE_A") (pintype "passive"))
      (node (ref "D3") (pin "A") (pinfunction "ANODE_A") (pintype "passive"))
      (node (ref "Q15") (pin "3") (pinfunction "D_3") (pintype "bidirectional"))
      (node (ref "R33") (pin "2") (pinfunction "2_2") (pintype "passive"))
      (node (ref "R47") (pin "2") (pinfunction "2_2") (pintype "passive"))
      (node (ref "R78") (pin "2") (pinfunction "2_2") (pintype "passive"))
    )
    (net (code "41") (name "C2DOFFG") (class "Default")
      (node (ref "Q15") (pin "1") (pinfunction "G_1") (pintype "bidirectional"))
      (node (ref "U17") (pin "A15") (pinfunction "A15_A15") (pintype "bidirectional"))
    )
    (net (code "42") (name "DI") (class "Default")
      (node (ref "Q16") (pin "1") (pinfunction "G_1") (pintype "bidirectional"))
      (node (ref "U17") (pin "B13") (pinfunction "B13_B13") (pintype "bidirectional"))
    )
    (net (code "43") (name "DI2") (class "Default")
      (node (ref "JP1") (pin "2") (pinfunction "2_2") (pintype "passive"))
      (node (ref "LED7") (pin "2-DOUT") (pinfunction "DOUT_2-DOUT") (pintype "output"))
    )
    (net (code "44") (name "FANON") (class "Default")
      (node (ref "Q9") (pin "1") (pinfunction "G_1") (pintype "bidirectional"))
      (node (ref "R34") (pin "2") (pinfunction "2_2") (pintype "passive"))
      (node (ref "U17") (pin "B4") (pinfunction "B4_B4") (pintype "bidirectional"))
    )
    (net (code "45") (name "GND") (class "Default")
      (node (ref "C10") (pin "2") (pinfunction "2_2") (pintype "passive"))
      (node (ref "C11") (pin "2") (pinfunction "2_2") (pintype "passive"))
      (node (ref "C13") (pin "2") (pinfunction "2_2") (pintype "passive"))
      (node (ref "C14") (pin "2") (pinfunction "2_2") (pintype "passive"))
      (node (ref "C16") (pin "2") (pinfunction "2_2") (pintype "passive"))
      (node (ref "C17") (pin "2") (pinfunction "2_2") (pintype "passive"))
      (node (ref "C18") (pin "2") (pinfunction "2_2") (pintype "passive"))
      (node (ref "C19") (pin "2") (pinfunction "2_2") (pintype "passive"))
      (node (ref "C2") (pin "2") (pinfunction "2_2") (pintype "passive"))
      (node (ref "C20") (pin "2") (pinfunction "2_2") (pintype "passive"))
      (node (ref "C21") (pin "2") (pinfunction "2_2") (pintype "passive"))
      (node (ref "C22") (pin "2") (pinfunction "2_2") (pintype "passive"))
      (node (ref "C24") (pin "2") (pinfunction "2_2") (pintype "passive"))
      (node (ref "C26") (pin "-") (pinfunction "-_-") (pintype "passive"))
      (node (ref "C27") (pin "2") (pinfunction "2_2") (pintype "passive"))
      (node (ref "C28") (pin "2") (pinfunction "2_2") (pintype "passive"))
      (node (ref "C29") (pin "2") (pinfunction "2_2") (pintype "passive"))
      (node (ref "C3") (pin "2") (pinfunction "2_2") (pintype "passive"))
      (node (ref "C30") (pin "2") (pinfunction "2_2") (pintype "passive"))
      (node (ref "C31") (pin "2") (pinfunction "2_2") (pintype "passive"))
      (node (ref "C32") (pin "-") (pinfunction "-_-") (pintype "passive"))
      (node (ref "C33") (pin "2") (pinfunction "2_2") (pintype "passive"))
      (node (ref "C34") (pin "2") (pinfunction "2_2") (pintype "passive"))
      (node (ref "C35") (pin "2") (pinfunction "2_2") (pintype "passive"))
      (node (ref "C37") (pin "2") (pinfunction "2_2") (pintype "passive"))
      (node (ref "C38") (pin "2") (pinfunction "2_2") (pintype "passive"))
      (node (ref "C39") (pin "2") (pinfunction "2_2") (pintype "passive"))
      (node (ref "C4") (pin "2") (pinfunction "2_2") (pintype "passive"))
      (node (ref "C41") (pin "2") (pinfunction "2_2") (pintype "passive"))
      (node (ref "C42") (pin "2") (pinfunction "2_2") (pintype "passive"))
      (node (ref "C43") (pin "2") (pinfunction "2_2") (pintype "passive"))
      (node (ref "C45") (pin "2") (pinfunction "2_2") (pintype "passive"))
      (node (ref "C46") (pin "2") (pinfunction "2_2") (pintype "passive"))
      (node (ref "C50") (pin "2") (pinfunction "2_2") (pintype "passive"))
      (node (ref "C51") (pin "2") (pinfunction "2_2") (pintype "passive"))
      (node (ref "C6") (pin "2") (pinfunction "2_2") (pintype "passive"))
      (node (ref "C7") (pin "-") (pinfunction "-_-") (pintype "passive"))
      (node (ref "C8") (pin "2") (pinfunction "2_2") (pintype "passive"))
      (node (ref "C9") (pin "2") (pinfunction "2_2") (pintype "passive"))
      (node (ref "D6") (pin "A") (pinfunction "ANODE_A") (pintype "passive"))
      (node (ref "D9") (pin "A") (pinfunction "ANODE_A") (pintype "passive"))
      (node (ref "J1") (pin "1") (pinfunction "1_1") (pintype "passive"))
      (node (ref "J4") (pin "1") (pinfunction "1_1") (pintype "passive"))
      (node (ref "J5") (pin "S2") (pinfunction "S2_S2") (pintype "bidirectional"))
      (node (ref "J6") (pin "1") (pinfunction "1_1") (pintype "passive"))
      (node (ref "JP1") (pin "1") (pinfunction "1_1") (pintype "passive"))
      (node (ref "LED7") (pin "3-GND") (pinfunction "GND_3-GND") (pintype "bidirectional"))
      (node (ref "Q1") (pin "1") (pinfunction "S_1") (pintype "bidirectional"))
      (node (ref "Q1") (pin "2") (pinfunction "S_2") (pintype "bidirectional"))
      (node (ref "Q1") (pin "3") (pinfunction "S_3") (pintype "bidirectional"))
      (node (ref "Q11") (pin "3") (pinfunction "C_3") (pintype "bidirectional"))
      (node (ref "Q13") (pin "3") (pinfunction "C_3") (pintype "bidirectional"))
      (node (ref "Q14") (pin "2") (pinfunction "S_2") (pintype "bidirectional"))
      (node (ref "Q15") (pin "2") (pinfunction "S_2") (pintype "bidirectional"))
      (node (ref "Q16") (pin "2") (pinfunction "S_2") (pintype "bidirectional"))
      (node (ref "Q17") (pin "1") (pinfunction "S_1") (pintype "bidirectional"))
      (node (ref "Q17") (pin "2") (pinfunction "S_2") (pintype "bidirectional"))
      (node (ref "Q17") (pin "3") (pinfunction "S_3") (pintype "bidirectional"))
      (node (ref "Q3") (pin "2") (pinfunction "S_2") (pintype "bidirectional"))
      (node (ref "Q7") (pin "1") (pinfunction "S_1") (pintype "bidirectional"))
      (node (ref "Q7") (pin "2") (pinfunction "S_2") (pintype "bidirectional"))
      (node (ref "Q7") (pin "3") (pinfunction "S_3") (pintype "bidirectional"))
      (node (ref "Q8") (pin "1") (pinfunction "S_1") (pintype "bidirectional"))
      (node (ref "Q8") (pin "2") (pinfunction "S_2") (pintype "bidirectional"))
      (node (ref "Q8") (pin "3") (pinfunction "S_3") (pintype "bidirectional"))
      (node (ref "Q9") (pin "2") (pinfunction "S_2") (pintype "bidirectional"))
      (node (ref "R1") (pin "2") (pinfunction "2_2") (pintype "passive"))
      (node (ref "R11") (pin "2") (pinfunction "2_2") (pintype "passive"))
      (node (ref "R13") (pin "1") (pinfunction "1_1") (pintype "passive"))
      (node (ref "R19") (pin "1") (pinfunction "1_1") (pintype "passive"))
      (node (ref "R2") (pin "2") (pinfunction "2_2") (pintype "passive"))
      (node (ref "R23") (pin "2") (pinfunction "2_2") (pintype "passive"))
      (node (ref "R24") (pin "2") (pinfunction "2_2") (pintype "passive"))
      (node (ref "R32") (pin "1") (pinfunction "1_1") (pintype "passive"))
      (node (ref "R34") (pin "1") (pinfunction "1_1") (pintype "passive"))
      (node (ref "R35") (pin "2") (pinfunction "2_2") (pintype "passive"))
      (node (ref "R39") (pin "1") (pinfunction "1_1") (pintype "passive"))
      (node (ref "R4") (pin "2") (pinfunction "2_2") (pintype "passive"))
      (node (ref "R46") (pin "1") (pinfunction "1_1") (pintype "passive"))
      (node (ref "R50") (pin "2") (pinfunction "2_2") (pintype "passive"))
      (node (ref "R51") (pin "2") (pinfunction "2_2") (pintype "passive"))
      (node (ref "R57") (pin "1") (pinfunction "1_1") (pintype "passive"))
      (node (ref "R59") (pin "2") (pinfunction "2_2") (pintype "passive"))
      (node (ref "R65") (pin "1") (pinfunction "1_1") (pintype "passive"))
      (node (ref "R68") (pin "1") (pinfunction "1_1") (pintype "passive"))
      (node (ref "R69") (pin "2") (pinfunction "2_2") (pintype "passive"))
      (node (ref "R74") (pin "2") (pinfunction "2_2") (pintype "passive"))
      (node (ref "R76") (pin "1") (pinfunction "1_1") (pintype "passive"))
      (node (ref "R80") (pin "2") (pinfunction "2_2") (pintype "passive"))
      (node (ref "R84") (pin "1") (pinfunction "1_1") (pintype "passive"))
      (node (ref "R86") (pin "1") (pinfunction "1_1") (pintype "passive"))
      (node (ref "R87") (pin "1") (pinfunction "1_1") (pintype "passive"))
      (node (ref "R94") (pin "1") (pinfunction "1_1") (pintype "passive"))
      (node (ref "S1") (pin "3") (pinfunction "3_3") (pintype "passive"))
      (node (ref "S1") (pin "4") (pinfunction "4_4") (pintype "passive"))
      (node (ref "S2") (pin "3") (pinfunction "3_3") (pintype "passive"))
      (node (ref "S2") (pin "4") (pinfunction "4_4") (pintype "passive"))
      (node (ref "T1") (pin "1") (pinfunction "1_1") (pintype "bidirectional"))
      (node (ref "T2") (pin "1") (pinfunction "1_1") (pintype "bidirectional"))
      (node (ref "U1") (pin "2") (pinfunction "GND_2") (pintype "bidirectional"))
      (node (ref "U11") (pin "4") (pinfunction "GND_4") (pintype "power_in"))
      (node (ref "U13") (pin "2") (pinfunction "VSS_2") (pintype "bidirectional"))
      (node (ref "U15") (pin "2") (pinfunction "GND_2") (pintype "bidirectional"))
      (node (ref "U16") (pin "2") (pinfunction "GND_2") (pintype "bidirectional"))
      (node (ref "U16") (pin "2@1") (pinfunction "GND_2@1") (pintype "bidirectional"))
      (node (ref "U17") (pin "GND") (pinfunction "GND_GND") (pintype "bidirectional"))
      (node (ref "U17") (pin "GND2") (pinfunction "GND2_GND2") (pintype "bidirectional"))
      (node (ref "U17") (pin "GND4") (pinfunction "GND4_GND4") (pintype "bidirectional"))
      (node (ref "U18") (pin "2") (pinfunction "GND_2") (pintype "bidirectional"))
      (node (ref "U2") (pin "9") (pinfunction "VSS_9") (pintype "bidirectional"))
      (node (ref "U3") (pin "2") (pinfunction "VSS_2") (pintype "bidirectional"))
      (node (ref "U5") (pin "2") (pinfunction "GND_2") (pintype "bidirectional"))
      (node (ref "U6") (pin "3") (pinfunction "A_3") (pintype "passive"))
      (node (ref "U7") (pin "2") (pinfunction "VSS_2") (pintype "bidirectional"))
      (node (ref "U8") (pin "2") (pinfunction "VSS_2") (pintype "bidirectional"))
      (node (ref "U9") (pin "2") (pinfunction "GND_2") (pintype "bidirectional"))
    )
    (net (code "46") (name "HIN") (class "Default")
      (node (ref "R42") (pin "1") (pinfunction "1_1") (pintype "passive"))
      (node (ref "U2") (pin "8") (pinfunction "IN_8") (pintype "bidirectional"))
    )
    (net (code "47") (name "HSTH") (class "Default")
      (node (ref "C41") (pin "1") (pinfunction "1_1") (pintype "passive"))
      (node (ref "R77") (pin "1") (pinfunction "1_1") (pintype "passive"))
      (node (ref "T1") (pin "2") (pinfunction "2_2") (pintype "bidirectional"))
      (node (ref "U18") (pin "1") (pinfunction "2_1") (pintype "bidirectional"))
    )
    (net (code "48") (name "HSTH2") (class "Default")
      (node (ref "C43") (pin "1") (pinfunction "1_1") (pintype "passive"))
      (node (ref "R14") (pin "1") (pinfunction "1_1") (pintype "passive"))
      (node (ref "T2") (pin "2") (pinfunction "2_2") (pintype "bidirectional"))
      (node (ref "U15") (pin "3") (pinfunction "1_3") (pintype "bidirectional"))
    )
    (net (code "49") (name "ISNS_REF") (class "Default")
      (node (ref "C11") (pin "1") (pinfunction "1_1") (pintype "passive"))
      (node (ref "C17") (pin "1") (pinfunction "1_1") (pintype "passive"))
      (node (ref "C28") (pin "1") (pinfunction "1_1") (pintype "passive"))
      (node (ref "R10") (pin "2") (pinfunction "2_2") (pintype "passive"))
      (node (ref "R11") (pin "1") (pinfunction "1_1") (pintype "passive"))
      (node (ref "TP5") (pin "1") (pinfunction "1_1") (pintype "bidirectional"))
      (node (ref "U1") (pin "1") (pinfunction "REF_1") (pintype "bidirectional"))
      (node (ref "U17") (pin "A5") (pinfunction "A5_A5") (pintype "bidirectional"))
      (node (ref "U9") (pin "1") (pinfunction "REF_1") (pintype "bidirectional"))
    )
    (net (code "50") (name "Net-(C5-Pad1)") (class "Default")
      (node (ref "C5") (pin "1") (pinfunction "1_1") (pintype "passive"))
      (node (ref "R30") (pin "2") (pinfunction "2_2") (pintype "passive"))
    )
    (net (code "51") (name "Net-(C12-Pad1)") (class "Default")
      (node (ref "C12") (pin "1") (pinfunction "1_1") (pintype "passive"))
      (node (ref "R40") (pin "2") (pinfunction "2_2") (pintype "passive"))
    )
    (net (code "52") (name "Net-(C15-Pad1)") (class "Default")
      (node (ref "C15") (pin "1") (pinfunction "1_1") (pintype "passive"))
      (node (ref "R64") (pin "2") (pinfunction "2_2") (pintype "passive"))
    )
    (net (code "53") (name "Net-(C23-Pad1)") (class "Default")
      (node (ref "C23") (pin "1") (pinfunction "1_1") (pintype "passive"))
      (node (ref "R55") (pin "2") (pinfunction "2_2") (pintype "passive"))
    )
    (net (code "54") (name "Net-(D1-CATHODE)") (class "Default")
      (node (ref "C1") (pin "1") (pinfunction "1_1") (pintype "passive"))
      (node (ref "D1") (pin "K") (pinfunction "CATHODE_K") (pintype "passive"))
      (node (ref "U2") (pin "2") (pinfunction "HB_2") (pintype "bidirectional"))
    )
    (net (code "55") (name "Net-(D2-CATHODE)") (class "Default")
      (node (ref "D2") (pin "K") (pinfunction "CATHODE_K") (pintype "passive"))
      (node (ref "R29") (pin "2") (pinfunction "2_2") (pintype "passive"))
      (node (ref "R30") (pin "1") (pinfunction "1_1") (pintype "passive"))
      (node (ref "U3") (pin "3") (pinfunction "VIN-_3") (pintype "bidirectional"))
    )
    (net (code "56") (name "Net-(D3-CATHODE)") (class "Default")
      (node (ref "D3") (pin "K") (pinfunction "CATHODE_K") (pintype "passive"))
      (node (ref "R38") (pin "2") (pinfunction "2_2") (pintype "passive"))
      (node (ref "R40") (pin "1") (pinfunction "1_1") (pintype "passive"))
      (node (ref "U7") (pin "3") (pinfunction "VIN-_3") (pintype "bidirectional"))
    )
    (net (code "57") (name "Net-(D4-CATHODE)") (class "Default")
      (node (ref "D4") (pin "K") (pinfunction "CATHODE_K") (pintype "passive"))
      (node (ref "R54") (pin "2") (pinfunction "2_2") (pintype "passive"))
      (node (ref "R55") (pin "1") (pinfunction "1_1") (pintype "passive"))
      (node (ref "U8") (pin "3") (pinfunction "VIN-_3") (pintype "bidirectional"))
    )
    (net (code "58") (name "Net-(D5-ANODE)") (class "Default")
      (node (ref "D5") (pin "A") (pinfunction "ANODE_A") (pintype "passive"))
      (node (ref "R6") (pin "2") (pinfunction "2_2") (pintype "passive"))
    )
    (net (code "59") (name "Net-(D5-CATHODE)") (class "Default")
      (node (ref "D5") (pin "K") (pinfunction "CATHODE_K") (pintype "passive"))
      (node (ref "Q10") (pin "1") (pinfunction "B_1") (pintype "bidirectional"))
      (node (ref "Q11") (pin "1") (pinfunction "B_1") (pintype "bidirectional"))
      (node (ref "R49") (pin "1") (pinfunction "1_1") (pintype "passive"))
    )
    (net (code "60") (name "Net-(D6-CATHODE)") (class "Default")
      (node (ref "C25") (pin "2") (pinfunction "2_2") (pintype "passive"))
      (node (ref "D6") (pin "K") (pinfunction "CATHODE_K") (pintype "passive"))
      (node (ref "L3") (pin "1") (pinfunction "P$1_1") (pintype "passive"))
      (node (ref "U5") (pin "6") (pinfunction "SW_6") (pintype "bidirectional"))
    )
    (net (code "61") (name "Net-(D11-CATHODE)") (class "Default")
      (node (ref "D11") (pin "K") (pinfunction "CATHODE_K") (pintype "passive"))
      (node (ref "R63") (pin "2") (pinfunction "2_2") (pintype "passive"))
      (node (ref "R64") (pin "1") (pinfunction "1_1") (pintype "passive"))
      (node (ref "U13") (pin "3") (pinfunction "VIN-_3") (pintype "bidirectional"))
    )
    (net (code "62") (name "Net-(J1-Pad2)") (class "Default")
      (node (ref "J1") (pin "2") (pinfunction "2_2") (pintype "passive"))
      (node (ref "R22") (pin "1") (pinfunction "1_1") (pintype "passive"))
    )
    (net (code "63") (name "Net-(L2-P$1)") (class "Default")
      (node (ref "C1") (pin "2") (pinfunction "2_2") (pintype "passive"))
      (node (ref "J5") (pin "D2") (pinfunction "D2_D2") (pintype "bidirectional"))
      (node (ref "J5") (pin "S1") (pinfunction "S1_S1") (pintype "bidirectional"))
      (node (ref "L2") (pin "1") (pinfunction "P$1_1") (pintype "passive"))
      (node (ref "U2") (pin "4") (pinfunction "HS_4") (pintype "bidirectional"))
    )
    (net (code "64") (name "Net-(L2-P$2)") (class "Default")
      (node (ref "C18") (pin "1") (pinfunction "1_1") (pintype "passive"))
      (node (ref "C26") (pin "+") (pinfunction "+_+") (pintype "passive"))
      (node (ref "L2") (pin "2") (pinfunction "P$2_2") (pintype "passive"))
      (node (ref "L4") (pin "1") (pinfunction "P$1_1") (pintype "passive"))
    )
    (net (code "65") (name "Net-(LED7-DIN)") (class "Default")
      (node (ref "LED7") (pin "4-DIN") (pinfunction "DIN_4-DIN") (pintype "input"))
      (node (ref "Q16") (pin "3") (pinfunction "D_3") (pintype "bidirectional"))
      (node (ref "R41") (pin "2") (pinfunction "2_2") (pintype "passive"))
    )
    (net (code "66") (name "Net-(Q2-G)") (class "Default")
      (node (ref "Q2") (pin "1") (pinfunction "G_1") (pintype "bidirectional"))
      (node (ref "R43") (pin "1") (pinfunction "1_1") (pintype "passive"))
    )
    (net (code "67") (name "Net-(Q4-G)") (class "Default")
      (node (ref "Q4") (pin "1") (pinfunction "G_1") (pintype "bidirectional"))
      (node (ref "R8") (pin "1") (pinfunction "1_1") (pintype "passive"))
    )
    (net (code "68") (name "Net-(Q5-G)") (class "Default")
      (node (ref "Q5") (pin "1") (pinfunction "G_1") (pintype "bidirectional"))
      (node (ref "R27") (pin "1") (pinfunction "1_1") (pintype "passive"))
    )
    (net (code "69") (name "Net-(Q6-G)") (class "Default")
      (node (ref "Q6") (pin "1") (pinfunction "G_1") (pintype "bidirectional"))
      (node (ref "R26") (pin "1") (pinfunction "1_1") (pintype "passive"))
    )
    (net (code "70") (name "Net-(Q9-D)") (class "Default")
      (node (ref "J2") (pin "2") (pinfunction "2_2") (pintype "passive"))
      (node (ref "Q9") (pin "3") (pinfunction "D_3") (pintype "bidirectional"))
    )
    (net (code "71") (name "Net-(Q12-B)") (class "Default")
      (node (ref "Q12") (pin "1") (pinfunction "B_1") (pintype "bidirectional"))
      (node (ref "Q13") (pin "1") (pinfunction "B_1") (pintype "bidirectional"))
      (node (ref "R66") (pin "1") (pinfunction "1_1") (pintype "passive"))
    )
    (net (code "72") (name "Net-(Q12-E)") (class "Default")
      (node (ref "Q12") (pin "2") (pinfunction "E_2") (pintype "bidirectional"))
      (node (ref "Q13") (pin "2") (pinfunction "E_2") (pintype "bidirectional"))
      (node (ref "R49") (pin "2") (pinfunction "2_2") (pintype "passive"))
      (node (ref "R6") (pin "1") (pinfunction "1_1") (pintype "passive"))
    )
    (net (code "73") (name "Net-(Q14-D)") (class "Default")
      (node (ref "Q14") (pin "3") (pinfunction "D_3") (pintype "bidirectional"))
      (node (ref "R60") (pin "2") (pinfunction "2_2") (pintype "passive"))
      (node (ref "R66") (pin "2") (pinfunction "2_2") (pintype "passive"))
    )
    (net (code "74") (name "Net-(R28-Pad1)") (class "Default")
      (node (ref "R28") (pin "1") (pinfunction "1_1") (pintype "passive"))
      (node (ref "R31") (pin "2") (pinfunction "2_2") (pintype "passive"))
      (node (ref "R32") (pin "2") (pinfunction "2_2") (pintype "passive"))
    )
    (net (code "75") (name "Net-(R36-Pad1)") (class "Default")
      (node (ref "R36") (pin "1") (pinfunction "1_1") (pintype "passive"))
      (node (ref "R44") (pin "2") (pinfunction "2_2") (pintype "passive"))
      (node (ref "R46") (pin "2") (pinfunction "2_2") (pintype "passive"))
    )
    (net (code "76") (name "Net-(R52-Pad1)") (class "Default")
      (node (ref "R52") (pin "1") (pinfunction "1_1") (pintype "passive"))
      (node (ref "R56") (pin "2") (pinfunction "2_2") (pintype "passive"))
      (node (ref "R57") (pin "2") (pinfunction "2_2") (pintype "passive"))
    )
    (net (code "77") (name "Net-(R61-Pad1)") (class "Default")
      (node (ref "R61") (pin "1") (pinfunction "1_1") (pintype "passive"))
      (node (ref "R62") (pin "2") (pinfunction "2_2") (pintype "passive"))
      (node (ref "R65") (pin "2") (pinfunction "2_2") (pintype "passive"))
    )
    (net (code "78") (name "Net-(R83-Pad2)") (class "Default")
      (node (ref "R83") (pin "2") (pinfunction "2_2") (pintype "passive"))
      (node (ref "R84") (pin "2") (pinfunction "2_2") (pintype "passive"))
      (node (ref "R85") (pin "1") (pinfunction "1_1") (pintype "passive"))
    )
    (net (code "79") (name "Net-(U1-OUT)") (class "Default")
      (node (ref "R12") (pin "1") (pinfunction "1_1") (pintype "passive"))
      (node (ref "U1") (pin "6") (pinfunction "OUT_6") (pintype "bidirectional"))
    )
    (net (code "80") (name "Net-(U1-VCC)") (class "Default")
      (node (ref "C14") (pin "1") (pinfunction "1_1") (pintype "passive"))
      (node (ref "R73") (pin "2") (pinfunction "2_2") (pintype "passive"))
      (node (ref "U1") (pin "3") (pinfunction "VCC_3") (pintype "bidirectional"))
    )
    (net (code "81") (name "Net-(U2-HO)") (class "Default")
      (node (ref "R17") (pin "1") (pinfunction "1_1") (pintype "passive"))
      (node (ref "U2") (pin "3") (pinfunction "HO_3") (pintype "bidirectional"))
    )
    (net (code "82") (name "Net-(U2-LO)") (class "Default")
      (node (ref "R3") (pin "1") (pinfunction "1_1") (pintype "passive"))
      (node (ref "U2") (pin "10") (pinfunction "LO_10") (pintype "bidirectional"))
    )
    (net (code "83") (name "Net-(U2-RDT)") (class "Default")
      (node (ref "R86") (pin "2") (pinfunction "2_2") (pintype "passive"))
      (node (ref "U2") (pin "6") (pinfunction "RDT_6") (pintype "bidirectional"))
    )
    (net (code "84") (name "Net-(U5-BST)") (class "Default")
      (node (ref "C25") (pin "1") (pinfunction "1_1") (pintype "passive"))
      (node (ref "U5") (pin "1") (pinfunction "BST_1") (pintype "bidirectional"))
    )
    (net (code "85") (name "Net-(U5-EN)") (class "Default")
      (node (ref "R95") (pin "1") (pinfunction "1_1") (pintype "passive"))
      (node (ref "U5") (pin "4") (pinfunction "EN_4") (pintype "bidirectional"))
    )
    (net (code "86") (name "Net-(U5-FB)") (class "Default")
      (node (ref "R93") (pin "1") (pinfunction "1_1") (pintype "passive"))
      (node (ref "R94") (pin "2") (pinfunction "2_2") (pintype "passive"))
      (node (ref "U5") (pin "3") (pinfunction "FB_3") (pintype "bidirectional"))
    )
    (net (code "87") (name "Net-(U9-OUT)") (class "Default")
      (node (ref "R70") (pin "1") (pinfunction "1_1") (pintype "passive"))
      (node (ref "U9") (pin "6") (pinfunction "OUT_6") (pintype "bidirectional"))
    )
    (net (code "88") (name "Net-(U9-VCC)") (class "Default")
      (node (ref "C19") (pin "1") (pinfunction "1_1") (pintype "passive"))
      (node (ref "R71") (pin "1") (pinfunction "1_1") (pintype "passive"))
      (node (ref "U9") (pin "3") (pinfunction "VCC_3") (pintype "bidirectional"))
    )
    (net (code "89") (name "Net-(U11A-VIN+)") (class "Default")
      (node (ref "R75") (pin "2") (pinfunction "2_2") (pintype "passive"))
      (node (ref "R76") (pin "2") (pinfunction "2_2") (pintype "passive"))
      (node (ref "U11") (pin "3") (pinfunction "VIN+_3") (pintype "bidirectional"))
    )
    (net (code "90") (name "Net-(U11A-VIN-)") (class "Default")
      (node (ref "R79") (pin "2") (pinfunction "2_2") (pintype "passive"))
      (node (ref "R81") (pin "1") (pinfunction "1_1") (pintype "passive"))
      (node (ref "U11") (pin "2") (pinfunction "VIN-_2") (pintype "bidirectional"))
    )
    (net (code "91") (name "Net-(U11A-VOUT)") (class "Default")
      (node (ref "R81") (pin "2") (pinfunction "2_2") (pintype "passive"))
      (node (ref "R82") (pin "1") (pinfunction "1_1") (pintype "passive"))
      (node (ref "U11") (pin "1") (pinfunction "VOUT_1") (pintype "bidirectional"))
    )
    (net (code "92") (name "Net-(U11B-VIN+)") (class "Default")
      (node (ref "R18") (pin "2") (pinfunction "2_2") (pintype "passive"))
      (node (ref "R19") (pin "2") (pinfunction "2_2") (pintype "passive"))
      (node (ref "U11") (pin "5") (pinfunction "VIN+_5") (pintype "bidirectional"))
    )
    (net (code "93") (name "Net-(U11B-VIN-)") (class "Default")
      (node (ref "R20") (pin "2") (pinfunction "2_2") (pintype "passive"))
      (node (ref "R21") (pin "1") (pinfunction "1_1") (pintype "passive"))
      (node (ref "U11") (pin "6") (pinfunction "VIN-_6") (pintype "bidirectional"))
    )
    (net (code "94") (name "Net-(U11B-VOUT)") (class "Default")
      (node (ref "R16") (pin "1") (pinfunction "1_1") (pintype "passive"))
      (node (ref "R21") (pin "2") (pinfunction "2_2") (pintype "passive"))
      (node (ref "U11") (pin "7") (pinfunction "VOUT_7") (pintype "bidirectional"))
    )
    (net (code "95") (name "Net-(U17-A12{slash}D+)") (class "Default")
      (node (ref "R53") (pin "2") (pinfunction "2_2") (pintype "passive"))
      (node (ref "U17") (pin "A12") (pinfunction "A12/D+_A12") (pintype "bidirectional"))
    )
    (net (code "96") (name "OA1+") (class "Default")
      (node (ref "JP3") (pin "2") (pinfunction "2_2") (pintype "passive"))
      (node (ref "R18") (pin "1") (pinfunction "1_1") (pintype "passive"))
      (node (ref "R75") (pin "1") (pinfunction "1_1") (pintype "passive"))
    )
    (net (code "97") (name "OA1-") (class "Default")
      (node (ref "JP2") (pin "2") (pinfunction "2_2") (pintype "passive"))
      (node (ref "R20") (pin "1") (pinfunction "1_1") (pintype "passive"))
      (node (ref "R79") (pin "1") (pinfunction "1_1") (pintype "passive"))
    )
    (net (code "98") (name "PA8") (class "Default")
      (node (ref "R42") (pin "2") (pinfunction "2_2") (pintype "passive"))
      (node (ref "R80") (pin "1") (pinfunction "1_1") (pintype "passive"))
      (node (ref "U17") (pin "A8") (pinfunction "A8_A8") (pintype "bidirectional"))
    )
    (net (code "99") (name "PA9") (class "Default")
      (node (ref "R4") (pin "1") (pinfunction "1_1") (pintype "passive"))
      (node (ref "R45") (pin "2") (pinfunction "2_2") (pintype "passive"))
      (node (ref "U17") (pin "A9") (pinfunction "A9_A9") (pintype "bidirectional"))
    )
    (net (code "100") (name "PB5") (class "Default")
      (node (ref "U15") (pin "6") (pinfunction "SEL_6") (pintype "bidirectional"))
      (node (ref "U17") (pin "B5") (pinfunction "B5_B5") (pintype "bidirectional"))
    )
    (net (code "101") (name "PB8") (class "Default")
      (node (ref "U17") (pin "B8") (pinfunction "B8_B8") (pintype "bidirectional"))
    )
    (net (code "102") (name "PB12") (class "Default")
      (node (ref "U17") (pin "B12") (pinfunction "B12_B12") (pintype "bidirectional"))
      (node (ref "U18") (pin "6") (pinfunction "SEL_6") (pintype "bidirectional"))
    )
    (net (code "103") (name "RS+") (class "Default")
      (node (ref "J3") (pin "2") (pinfunction "2_2") (pintype "passive"))
      (node (ref "JP3") (pin "1") (pinfunction "1_1") (pintype "passive"))
    )
    (net (code "104") (name "RS-") (class "Default")
      (node (ref "J3") (pin "1") (pinfunction "1_1") (pintype "passive"))
      (node (ref "JP2") (pin "1") (pinfunction "1_1") (pintype "passive"))
    )
    (net (code "105") (name "S1") (class "Default")
      (node (ref "S1") (pin "1") (pinfunction "1_1") (pintype "passive"))
      (node (ref "U17") (pin "B9") (pinfunction "B9_B9") (pintype "bidirectional"))
    )
    (net (code "106") (name "S2") (class "Default")
      (node (ref "S2") (pin "1") (pinfunction "1_1") (pintype "passive"))
      (node (ref "U17") (pin "C13") (pinfunction "C13_C13") (pintype "bidirectional"))
    )
    (net (code "107") (name "SCL-TX") (class "Default")
      (node (ref "U17") (pin "B10") (pinfunction "B10_B10") (pintype "bidirectional"))
    )
    (net (code "108") (name "SDA-RX") (class "Default")
      (node (ref "U17") (pin "B11") (pinfunction "B11_B11") (pintype "bidirectional"))
    )
    (net (code "109") (name "VS") (class "Default")
      (node (ref "C13") (pin "1") (pinfunction "1_1") (pintype "passive"))
      (node (ref "C7") (pin "+") (pinfunction "+_+") (pintype "passive"))
      (node (ref "J5") (pin "D1") (pinfunction "D1_D1") (pintype "bidirectional"))
      (node (ref "J6") (pin "2") (pinfunction "2_2") (pintype "passive"))
      (node (ref "R85") (pin "2") (pinfunction "2_2") (pintype "passive"))
    )
    (net (code "110") (name "unconnected-(S1-Pad2)") (class "Default")
      (node (ref "S1") (pin "2") (pinfunction "2_2") (pintype "passive"))
    )
    (net (code "111") (name "unconnected-(S2-Pad2)") (class "Default")
      (node (ref "S2") (pin "2") (pinfunction "2_2") (pintype "passive"))
    )
    (net (code "112") (name "unconnected-(U17-PadA2)") (class "Default")
      (node (ref "U17") (pin "A2") (pinfunction "A2_A2") (pintype "bidirectional"))
    )
    (net (code "113") (name "unconnected-(U17-PadA10)") (class "Default")
      (node (ref "U17") (pin "A10") (pinfunction "A10_A10") (pintype "bidirectional"))
    )
    (net (code "114") (name "unconnected-(U17-PadB3)") (class "Default")
      (node (ref "U17") (pin "B3") (pinfunction "B3_B3") (pintype "bidirectional"))
    )
    (net (code "115") (name "unconnected-(U17-PadB7)") (class "Default")
      (node (ref "U17") (pin "B7") (pinfunction "B7_B7") (pintype "bidirectional"))
    )
    (net (code "116") (name "unconnected-(U17-PadRST)") (class "Default")
      (node (ref "U17") (pin "RST") (pinfunction "RST_RST") (pintype "bidirectional"))
    )
    (net (code "117") (name "unconnected-(U17-VB-PadVBAT)") (class "Default")
      (node (ref "U17") (pin "VBAT") (pinfunction "VB_VBAT") (pintype "bidirectional"))
    )
  )
)
